# 1-Schematic_fefr.net
KiCad netlist of a schematic drawn in EasyEDA
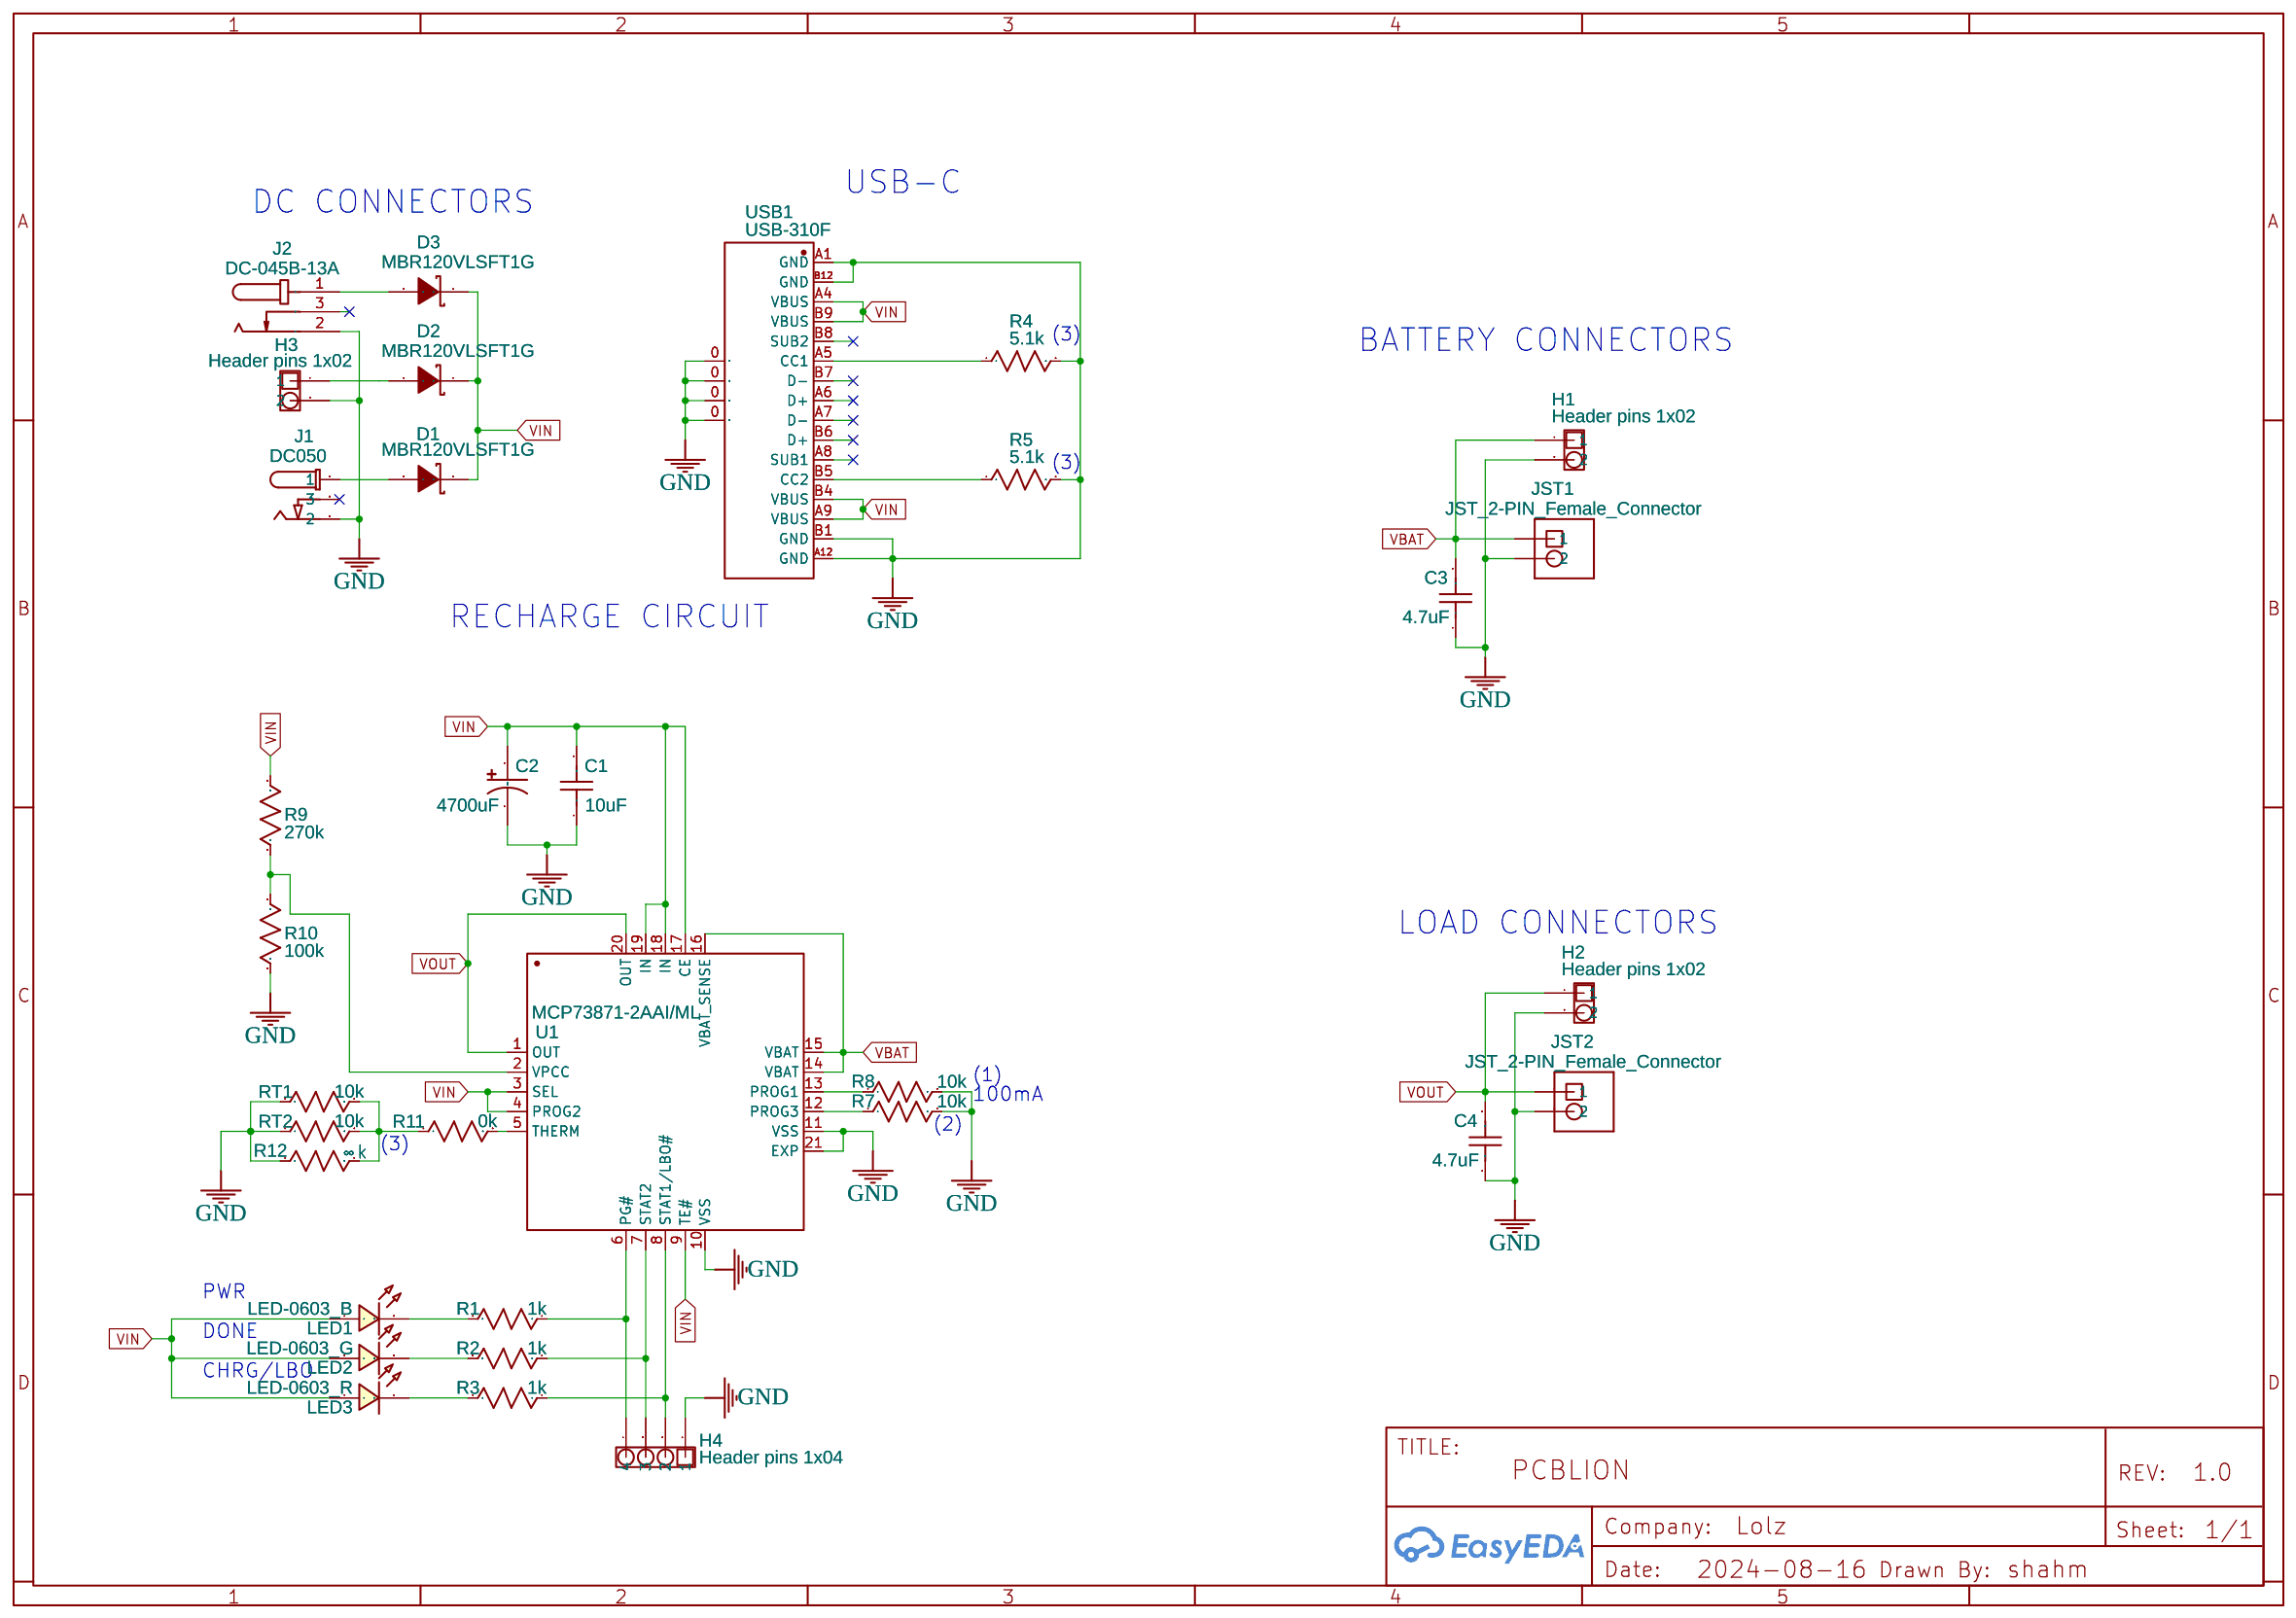
[diagram p0: schematic sheet]

(export (version "E")
  (design (tool "Eeschema 10.0.6"))
  (components
    (comp (ref "C1") (value "10uF") (libsource (lib "") (part "C_0603_US")))
    (comp (ref "C2")
      (value "4700uF")
      (fields (field (name "Manufacturer Part") "EEUFR1A472L") (field (name "Manufacturer") "PANASONIC"))
      (libsource (lib "") (part "EEUFR1A472L"))
    )
    (comp (ref "C3") (value "4.7uF") (libsource (lib "") (part "C_0603_US")))
    (comp (ref "C4") (value "4.7uF") (libsource (lib "") (part "C_0603_US")))
    (comp (ref "D1")
      (value "MBR120VLSFT1G")
      (fields (field (name "Manufacturer") "ON Semicon"))
      (libsource (lib "") (part "MBR120VLSFT1G"))
    )
    (comp (ref "D2")
      (value "MBR120VLSFT1G")
      (fields (field (name "Manufacturer") "ON Semicon"))
      (libsource (lib "") (part "MBR120VLSFT1G"))
    )
    (comp (ref "D3")
      (value "MBR120VLSFT1G")
      (fields (field (name "Manufacturer") "ON Semicon"))
      (libsource (lib "") (part "MBR120VLSFT1G"))
    )
    (comp (ref "H1") (value "Header pins 1x02") (libsource (lib "") (part "Header pins 1x02")))
    (comp (ref "H2") (value "Header pins 1x02") (libsource (lib "") (part "Header pins 1x02")))
    (comp (ref "H3") (value "Header pins 1x02") (libsource (lib "") (part "Header pins 1x02_1")))
    (comp (ref "H4") (value "Header pins 1x04") (libsource (lib "") (part "Header pins 1x04")))
    (comp (ref "J1")
      (value "DC050")
      (fields (field (name "Manufacturer Part") "DC00050-A") (field (name "Manufacturer") "SHOU HAN"))
      (libsource (lib "") (part "DC050 DC POWER CONNECTOR"))
    )
    (comp (ref "J2")
      (value "DC-045B-13A")
      (fields (field (name "Manufacturer") "HRO"))
      (libsource (lib "") (part "DC-045B-13A"))
    )
    (comp (ref "JST1")
      (value "JST_2-PIN_Female_Connector")
      (libsource (lib "") (part "JST_2-PIN_Female_Connector"))
    )
    (comp (ref "JST2")
      (value "JST_2-PIN_Female_Connector")
      (libsource (lib "") (part "JST_2-PIN_Female_Connector"))
    )
    (comp (ref "LED1")
      (value "LED-0603_B")
      (fields
        (field (name "Manufacturer Part") "19-217/BHC-ZL1M2RY/3T")
        (field (name "Manufacturer") "EVERLIGHT(台湾亿光)")
      )
      (libsource (lib "") (part "LED-0603_B"))
    )
    (comp (ref "LED2")
      (value "LED-0603_G")
      (fields
        (field (name "Manufacturer Part") "19-217/GHC-YR1S2/3T")
        (field (name "Manufacturer") "EVERLIGHT(台湾亿光)")
      )
      (libsource (lib "") (part "LED-0603_G"))
    )
    (comp (ref "LED3")
      (value "LED-0603_R")
      (fields
        (field (name "Manufacturer Part") "19-217/R6C-AL1M2VY/3T")
        (field (name "Manufacturer") "EVERLIGHT(台湾亿光)")
      )
      (libsource (lib "") (part "LED-0603_R"))
    )
    (comp (ref "R1") (value "1k") (libsource (lib "") (part "R_0603_US")))
    (comp (ref "R2") (value "1k") (libsource (lib "") (part "R_0603_US")))
    (comp (ref "R3") (value "1k") (libsource (lib "") (part "R_0603_US")))
    (comp (ref "R4") (value "5.1k") (libsource (lib "") (part "R_0603_US_1")))
    (comp (ref "R5") (value "5.1k") (libsource (lib "") (part "R_0603_US_1")))
    (comp (ref "R7") (value "10k") (libsource (lib "") (part "R_0603_US_1")))
    (comp (ref "R8") (value "10k") (libsource (lib "") (part "R_0603_US_1")))
    (comp (ref "R9") (value "270k") (libsource (lib "") (part "R_0603_US_2")))
    (comp (ref "R10") (value "100k") (libsource (lib "") (part "R_0603_US_2")))
    (comp (ref "R11") (value "0k") (libsource (lib "") (part "R_0603_US_1")))
    (comp (ref "R12") (value "∞k") (libsource (lib "") (part "R_0603_US_1")))
    (comp (ref "RT1") (value "10k") (libsource (lib "") (part "R_0603_US_3")))
    (comp (ref "RT2") (value "10k") (libsource (lib "") (part "R_0603_US_3")))
    (comp (ref "U1")
      (value "MCP73871-2AAI/ML")
      (fields (field (name "Manufacturer") "MICROCHIP"))
      (libsource (lib "") (part "MCP73871-2AAI/ML"))
    )
    (comp (ref "USB1")
      (value "USB-310F")
      (fields (field (name "Manufacturer") "HOOYA"))
      (libsource (lib "") (part "USB-310F"))
    )
  )
  (nets
    (net (code "1") (name "GND") (class "Default")
      (node (ref "C1") (pin "1") (pinfunction "1_1") (pintype "unspecified"))
      (node (ref "C2") (pin "2") (pinfunction "2_2") (pintype "unspecified"))
      (node (ref "C3") (pin "1") (pinfunction "1_1") (pintype "unspecified"))
      (node (ref "C4") (pin "1") (pinfunction "1_1") (pintype "unspecified"))
      (node (ref "H1") (pin "2") (pinfunction "2_2") (pintype "unspecified"))
      (node (ref "H2") (pin "2") (pinfunction "2_2") (pintype "unspecified"))
      (node (ref "H3") (pin "2") (pinfunction "2_2") (pintype "unspecified"))
      (node (ref "H4") (pin "1") (pinfunction "1_1") (pintype "unspecified"))
      (node (ref "J1") (pin "2") (pinfunction "2_2") (pintype "unspecified"))
      (node (ref "J2") (pin "2") (pinfunction "2_2") (pintype "unspecified"))
      (node (ref "JST1") (pin "2") (pinfunction "2_2") (pintype "unspecified"))
      (node (ref "JST2") (pin "2") (pinfunction "2_2") (pintype "unspecified"))
      (node (ref "R10") (pin "1") (pinfunction "1_1") (pintype "unspecified"))
      (node (ref "R12") (pin "1") (pinfunction "1_1") (pintype "unspecified"))
      (node (ref "R4") (pin "2") (pinfunction "2_2") (pintype "unspecified"))
      (node (ref "R5") (pin "2") (pinfunction "2_2") (pintype "unspecified"))
      (node (ref "R7") (pin "2") (pinfunction "2_2") (pintype "unspecified"))
      (node (ref "R8") (pin "2") (pinfunction "2_2") (pintype "unspecified"))
      (node (ref "RT1") (pin "1") (pinfunction "1_1") (pintype "unspecified"))
      (node (ref "RT2") (pin "1") (pinfunction "1_1") (pintype "unspecified"))
      (node (ref "U1") (pin "10") (pinfunction "VSS_10") (pintype "unspecified"))
      (node (ref "U1") (pin "11") (pinfunction "VSS_11") (pintype "unspecified"))
      (node (ref "U1") (pin "21") (pinfunction "EXP_21") (pintype "unspecified"))
      (node (ref "USB1") (pin "0") (pinfunction "0_0") (pintype "unspecified"))
      (node (ref "USB1") (pin "A1") (pinfunction "GND_A1") (pintype "unspecified"))
      (node (ref "USB1") (pin "A12") (pinfunction "GND_A12") (pintype "unspecified"))
      (node (ref "USB1") (pin "B1") (pinfunction "GND_B1") (pintype "unspecified"))
      (node (ref "USB1") (pin "B12") (pinfunction "GND_B12") (pintype "unspecified"))
    )
    (net (code "2") (name "Net-(D1-A)") (class "Default")
      (node (ref "D1") (pin "2") (pinfunction "A_2") (pintype "unspecified"))
      (node (ref "J1") (pin "1") (pinfunction "1_1") (pintype "unspecified"))
    )
    (net (code "3") (name "Net-(D2-A)") (class "Default")
      (node (ref "D2") (pin "2") (pinfunction "A_2") (pintype "unspecified"))
      (node (ref "H3") (pin "1") (pinfunction "1_1") (pintype "unspecified"))
    )
    (net (code "4") (name "Net-(D3-A)") (class "Default")
      (node (ref "D3") (pin "2") (pinfunction "A_2") (pintype "unspecified"))
      (node (ref "J2") (pin "1") (pinfunction "1_1") (pintype "unspecified"))
    )
    (net (code "5") (name "Net-(LED1-Pad2)") (class "Default")
      (node (ref "LED1") (pin "2") (pinfunction "2_2") (pintype "unspecified"))
      (node (ref "R1") (pin "2") (pinfunction "2_2") (pintype "unspecified"))
    )
    (net (code "6") (name "Net-(LED2-Pad2)") (class "Default")
      (node (ref "LED2") (pin "2") (pinfunction "2_2") (pintype "unspecified"))
      (node (ref "R2") (pin "2") (pinfunction "2_2") (pintype "unspecified"))
    )
    (net (code "7") (name "Net-(LED3-Pad2)") (class "Default")
      (node (ref "LED3") (pin "2") (pinfunction "2_2") (pintype "unspecified"))
      (node (ref "R3") (pin "2") (pinfunction "2_2") (pintype "unspecified"))
    )
    (net (code "8") (name "Net-(R11-Pad1)") (class "Default")
      (node (ref "R11") (pin "1") (pinfunction "1_1") (pintype "unspecified"))
      (node (ref "R12") (pin "2") (pinfunction "2_2") (pintype "unspecified"))
      (node (ref "RT1") (pin "2") (pinfunction "2_2") (pintype "unspecified"))
      (node (ref "RT2") (pin "2") (pinfunction "2_2") (pintype "unspecified"))
    )
    (net (code "9") (name "Net-(U1-PG#)") (class "Default")
      (node (ref "H4") (pin "4") (pinfunction "4_4") (pintype "unspecified"))
      (node (ref "R1") (pin "1") (pinfunction "1_1") (pintype "unspecified"))
      (node (ref "U1") (pin "6") (pinfunction "PG#_6") (pintype "unspecified"))
    )
    (net (code "10") (name "Net-(U1-PROG1)") (class "Default")
      (node (ref "R8") (pin "1") (pinfunction "1_1") (pintype "unspecified"))
      (node (ref "U1") (pin "13") (pinfunction "PROG1_13") (pintype "unspecified"))
    )
    (net (code "11") (name "Net-(U1-PROG3)") (class "Default")
      (node (ref "R7") (pin "1") (pinfunction "1_1") (pintype "unspecified"))
      (node (ref "U1") (pin "12") (pinfunction "PROG3_12") (pintype "unspecified"))
    )
    (net (code "12") (name "Net-(U1-STAT1{slash}LBO#)") (class "Default")
      (node (ref "H4") (pin "2") (pinfunction "2_2") (pintype "unspecified"))
      (node (ref "R3") (pin "1") (pinfunction "1_1") (pintype "unspecified"))
      (node (ref "U1") (pin "8") (pinfunction "STAT1/LBO#_8") (pintype "unspecified"))
    )
    (net (code "13") (name "Net-(U1-STAT2)") (class "Default")
      (node (ref "H4") (pin "3") (pinfunction "3_3") (pintype "unspecified"))
      (node (ref "R2") (pin "1") (pinfunction "1_1") (pintype "unspecified"))
      (node (ref "U1") (pin "7") (pinfunction "STAT2_7") (pintype "unspecified"))
    )
    (net (code "14") (name "Net-(U1-THERM)") (class "Default")
      (node (ref "R11") (pin "2") (pinfunction "2_2") (pintype "unspecified"))
      (node (ref "U1") (pin "5") (pinfunction "THERM_5") (pintype "unspecified"))
    )
    (net (code "15") (name "Net-(U1-VPCC)") (class "Default")
      (node (ref "R10") (pin "2") (pinfunction "2_2") (pintype "unspecified"))
      (node (ref "R9") (pin "1") (pinfunction "1_1") (pintype "unspecified"))
      (node (ref "U1") (pin "2") (pinfunction "VPCC_2") (pintype "unspecified"))
    )
    (net (code "16") (name "Net-(USB1-CC1)") (class "Default")
      (node (ref "R4") (pin "1") (pinfunction "1_1") (pintype "unspecified"))
      (node (ref "USB1") (pin "A5") (pinfunction "CC1_A5") (pintype "unspecified"))
    )
    (net (code "17") (name "Net-(USB1-CC2)") (class "Default")
      (node (ref "R5") (pin "1") (pinfunction "1_1") (pintype "unspecified"))
      (node (ref "USB1") (pin "B5") (pinfunction "CC2_B5") (pintype "unspecified"))
    )
    (net (code "18") (name "VBAT") (class "Default")
      (node (ref "C3") (pin "2") (pinfunction "2_2") (pintype "unspecified"))
      (node (ref "H1") (pin "1") (pinfunction "1_1") (pintype "unspecified"))
      (node (ref "JST1") (pin "1") (pinfunction "1_1") (pintype "unspecified"))
      (node (ref "U1") (pin "14") (pinfunction "VBAT_14") (pintype "unspecified"))
      (node (ref "U1") (pin "15") (pinfunction "VBAT_15") (pintype "unspecified"))
      (node (ref "U1") (pin "16") (pinfunction "VBAT_SENSE_16") (pintype "unspecified"))
    )
    (net (code "19") (name "VIN") (class "Default")
      (node (ref "C1") (pin "2") (pinfunction "2_2") (pintype "unspecified"))
      (node (ref "C2") (pin "1") (pinfunction "1_1") (pintype "unspecified"))
      (node (ref "D1") (pin "1") (pinfunction "K_1") (pintype "unspecified"))
      (node (ref "D2") (pin "1") (pinfunction "K_1") (pintype "unspecified"))
      (node (ref "D3") (pin "1") (pinfunction "K_1") (pintype "unspecified"))
      (node (ref "LED1") (pin "1") (pinfunction "1_1") (pintype "unspecified"))
      (node (ref "LED2") (pin "1") (pinfunction "1_1") (pintype "unspecified"))
      (node (ref "LED3") (pin "1") (pinfunction "1_1") (pintype "unspecified"))
      (node (ref "R9") (pin "2") (pinfunction "2_2") (pintype "unspecified"))
      (node (ref "U1") (pin "17") (pinfunction "CE_17") (pintype "unspecified"))
      (node (ref "U1") (pin "18") (pinfunction "IN_18") (pintype "unspecified"))
      (node (ref "U1") (pin "19") (pinfunction "IN_19") (pintype "unspecified"))
      (node (ref "U1") (pin "3") (pinfunction "SEL_3") (pintype "unspecified"))
      (node (ref "U1") (pin "4") (pinfunction "PROG2_4") (pintype "unspecified"))
      (node (ref "U1") (pin "9") (pinfunction "TE#_9") (pintype "unspecified"))
      (node (ref "USB1") (pin "A4") (pinfunction "VBUS_A4") (pintype "unspecified"))
      (node (ref "USB1") (pin "A9") (pinfunction "VBUS_A9") (pintype "unspecified"))
      (node (ref "USB1") (pin "B4") (pinfunction "VBUS_B4") (pintype "unspecified"))
      (node (ref "USB1") (pin "B9") (pinfunction "VBUS_B9") (pintype "unspecified"))
    )
    (net (code "20") (name "VOUT") (class "Default")
      (node (ref "C4") (pin "2") (pinfunction "2_2") (pintype "unspecified"))
      (node (ref "H2") (pin "1") (pinfunction "1_1") (pintype "unspecified"))
      (node (ref "JST2") (pin "1") (pinfunction "1_1") (pintype "unspecified"))
      (node (ref "U1") (pin "1") (pinfunction "OUT_1") (pintype "unspecified"))
      (node (ref "U1") (pin "20") (pinfunction "OUT_20") (pintype "unspecified"))
    )
    (net (code "21") (name "unconnected-(J1-Pad3)") (class "Default")
      (node (ref "J1") (pin "3") (pinfunction "3_3") (pintype "unspecified+no_connect"))
    )
    (net (code "22") (name "unconnected-(J2-Pad3)") (class "Default")
      (node (ref "J2") (pin "3") (pinfunction "3_3") (pintype "unspecified+no_connect"))
    )
    (net (code "23") (name "unconnected-(USB1-D+-PadA6)") (class "Default")
      (node (ref "USB1") (pin "A6") (pinfunction "D+_A6") (pintype "unspecified+no_connect"))
    )
    (net (code "24") (name "unconnected-(USB1-D+-PadB6)") (class "Default")
      (node (ref "USB1") (pin "B6") (pinfunction "D+_B6") (pintype "unspecified+no_connect"))
    )
    (net (code "25") (name "unconnected-(USB1-D--PadA7)") (class "Default")
      (node (ref "USB1") (pin "A7") (pinfunction "D-_A7") (pintype "unspecified+no_connect"))
    )
    (net (code "26") (name "unconnected-(USB1-D--PadB7)") (class "Default")
      (node (ref "USB1") (pin "B7") (pinfunction "D-_B7") (pintype "unspecified+no_connect"))
    )
    (net (code "27") (name "unconnected-(USB1-SUB1-PadA8)") (class "Default")
      (node (ref "USB1") (pin "A8") (pinfunction "SUB1_A8") (pintype "unspecified+no_connect"))
    )
    (net (code "28") (name "unconnected-(USB1-SUB2-PadB8)") (class "Default")
      (node (ref "USB1") (pin "B8") (pinfunction "SUB2_B8") (pintype "unspecified+no_connect"))
    )
  )
)
